# SparkFun_VR_IMU_Breakout_BNO086_QWIIC.net
KiCad netlist of a schematic drawn in EAGLE
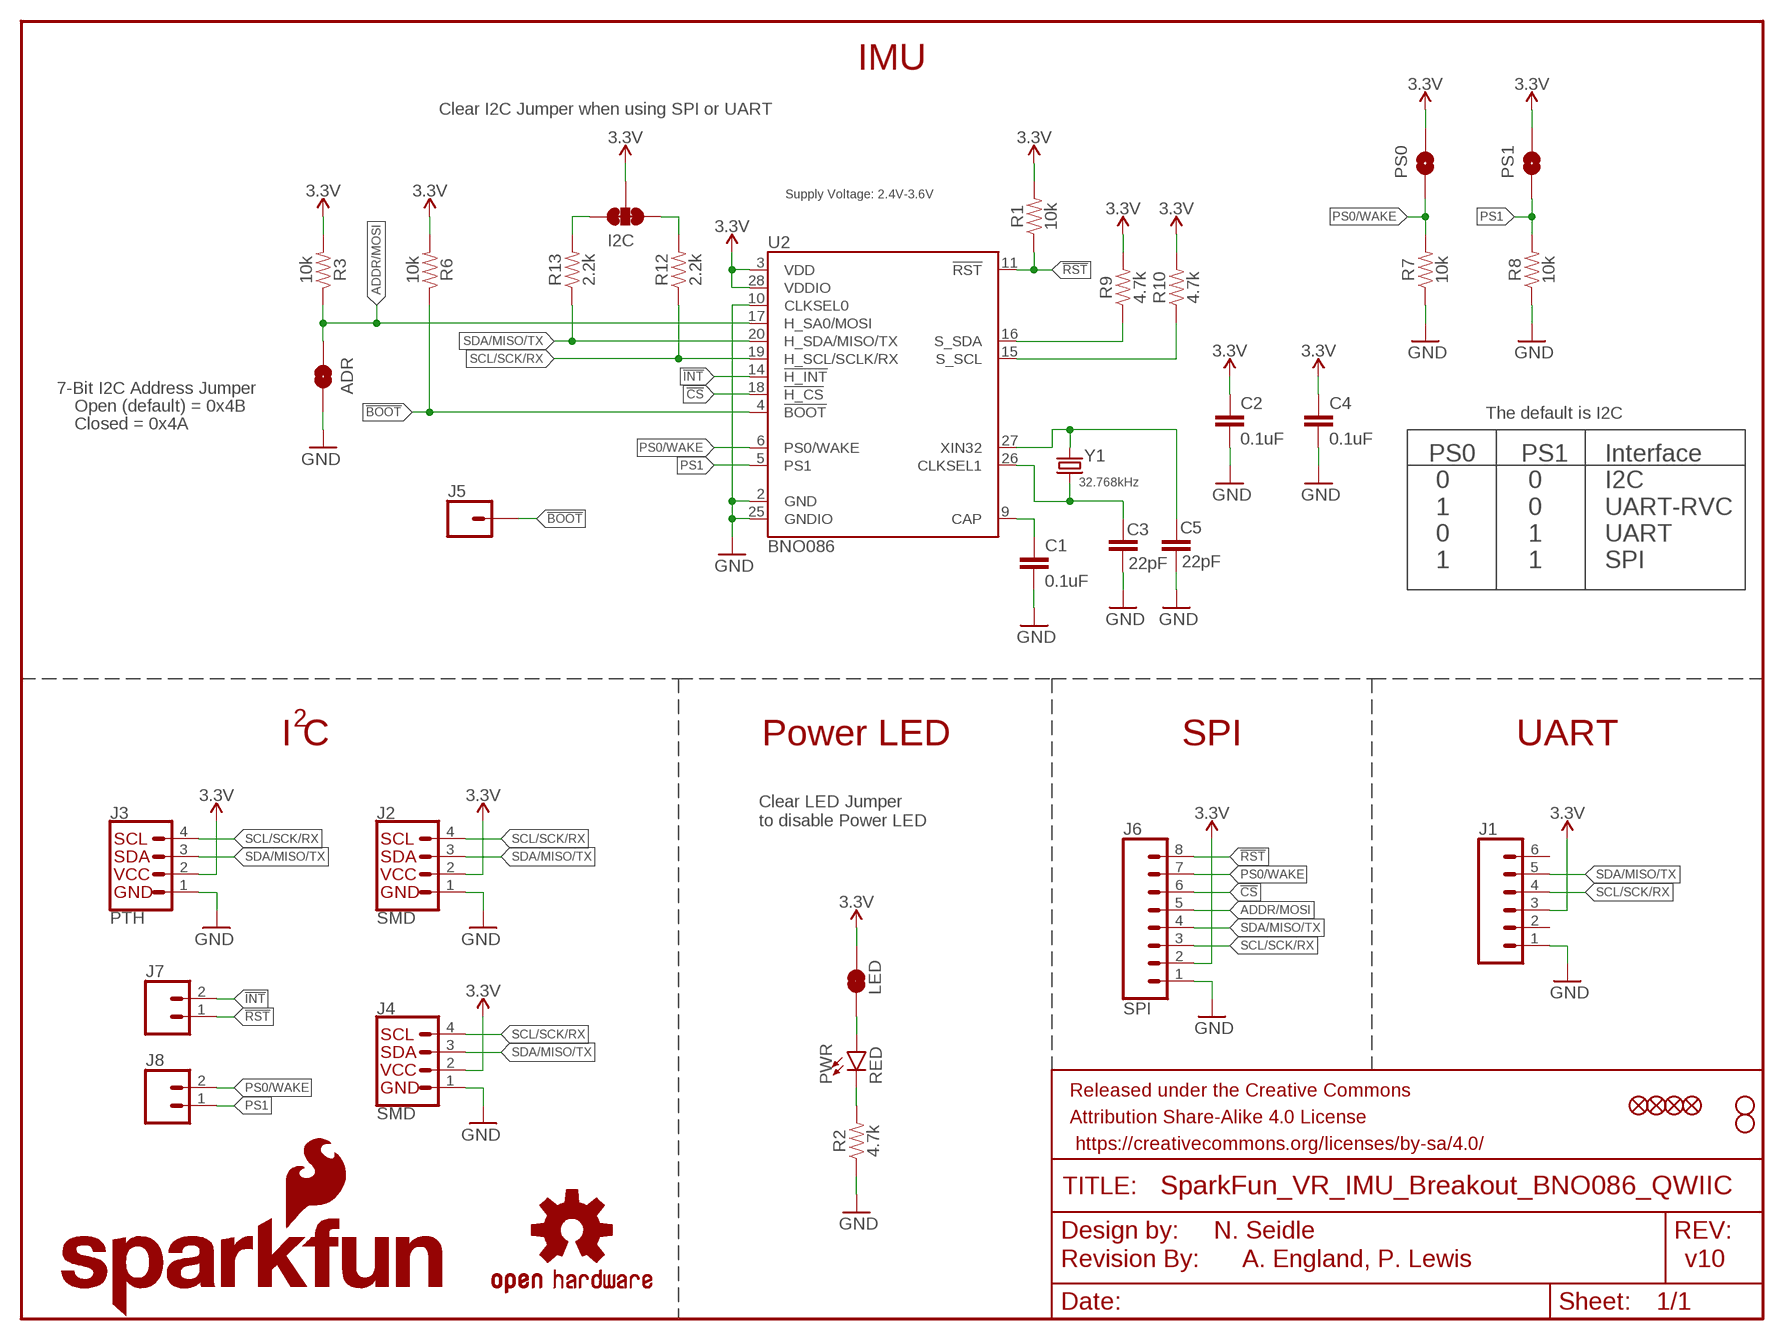
[diagram p0: schematic, sheet 1]

(export (version "E")
  (design (tool "Eeschema 10.0.6"))
  (components
    (comp (ref "ADR")
      (value "JUMPER-SMT_2_NO_SILK")
      (footprint "eagle-import:SMT-JUMPER_2_NO_SILK")
      (libsource (lib "eagle-import") (part "JUMPER-SMT_2_NO_SILK"))
    )
    (comp (ref "C1")
      (value "0.1uF")
      (footprint "eagle-import:0603")
      (libsource (lib "eagle-import") (part "0.1UF-0603-25V-(+80/-20%)"))
    )
    (comp (ref "C2")
      (value "0.1uF")
      (footprint "eagle-import:0603")
      (libsource (lib "eagle-import") (part "0.1UF-0603-25V-(+80/-20%)"))
    )
    (comp (ref "C3")
      (value "22pF")
      (footprint "eagle-import:0603")
      (libsource (lib "eagle-import") (part "22PF-0603-50V-5%"))
    )
    (comp (ref "C4")
      (value "0.1uF")
      (footprint "eagle-import:0603")
      (libsource (lib "eagle-import") (part "0.1UF-0603-25V-(+80/-20%)"))
    )
    (comp (ref "C5")
      (value "22pF")
      (footprint "eagle-import:0603")
      (libsource (lib "eagle-import") (part "22PF-0603-50V-5%"))
    )
    (comp (ref "FRAME1")
      (value "FRAME-LETTER")
      (footprint "eagle-import:CREATIVE_COMMONS")
      (libsource (lib "eagle-import") (part "FRAME-LETTER"))
    )
    (comp (ref "I2C")
      (value "JUMPER-SMT_3_2-NC_TRACE_SILK")
      (footprint "eagle-import:SMT-JUMPER_3_2-NC_TRACE_SILK")
      (libsource (lib "eagle-import") (part "JUMPER-SMT_3_2-NC_TRACE_SILK"))
    )
    (comp (ref "J1")
      (value "CONN_06NO_SILK_FEMALE_PTH")
      (footprint "eagle-import:1X06_NO_SILK")
      (libsource (lib "eagle-import") (part "CONN_06NO_SILK_FEMALE_PTH"))
    )
    (comp (ref "J2")
      (value "SMD")
      (footprint "eagle-import:JST04_1MM_RA")
      (libsource (lib "eagle-import") (part "QWIIC_CONNECTORJS-1MM"))
    )
    (comp (ref "J3")
      (value "PTH")
      (footprint "eagle-import:1X04_NO_SILK")
      (libsource (lib "eagle-import") (part "I2C_STANDARD_NO_SILK"))
    )
    (comp (ref "J4")
      (value "SMD")
      (footprint "eagle-import:JST04_1MM_RA")
      (libsource (lib "eagle-import") (part "QWIIC_CONNECTORJS-1MM"))
    )
    (comp (ref "J5")
      (value "CONN_01PTH_NO_SILK_YES_STOP")
      (footprint "eagle-import:1X01_NO_SILK")
      (libsource (lib "eagle-import") (part "CONN_01PTH_NO_SILK_YES_STOP"))
    )
    (comp (ref "J6")
      (value "SPI")
      (footprint "eagle-import:1X08_NO_SILK")
      (libsource (lib "eagle-import") (part "CONN_08NO_SILK_FEMALE_PTH"))
    )
    (comp (ref "J7")
      (value "CONN_021X02_NO_SILK")
      (footprint "eagle-import:1X02_NO_SILK")
      (libsource (lib "eagle-import") (part "CONN_021X02_NO_SILK"))
    )
    (comp (ref "J8")
      (value "CONN_021X02_NO_SILK")
      (footprint "eagle-import:1X02_NO_SILK")
      (libsource (lib "eagle-import") (part "CONN_021X02_NO_SILK"))
    )
    (comp (ref "JP1")
      (value "FIDUCIALUFIDUCIAL")
      (footprint "eagle-import:FIDUCIAL-MICRO")
      (libsource (lib "eagle-import") (part "FIDUCIALUFIDUCIAL"))
    )
    (comp (ref "JP2")
      (value "FIDUCIALUFIDUCIAL")
      (footprint "eagle-import:FIDUCIAL-MICRO")
      (libsource (lib "eagle-import") (part "FIDUCIALUFIDUCIAL"))
    )
    (comp (ref "JP3")
      (value "STAND-OFF")
      (footprint "eagle-import:STAND-OFF")
      (libsource (lib "eagle-import") (part "STAND-OFF"))
    )
    (comp (ref "JP4")
      (value "STAND-OFF")
      (footprint "eagle-import:STAND-OFF")
      (libsource (lib "eagle-import") (part "STAND-OFF"))
    )
    (comp (ref "JP5")
      (value "FIDUCIALUFIDUCIAL")
      (footprint "eagle-import:FIDUCIAL-MICRO")
      (libsource (lib "eagle-import") (part "FIDUCIALUFIDUCIAL"))
    )
    (comp (ref "JP6")
      (value "FIDUCIALUFIDUCIAL")
      (footprint "eagle-import:FIDUCIAL-MICRO")
      (libsource (lib "eagle-import") (part "FIDUCIALUFIDUCIAL"))
    )
    (comp (ref "LED")
      (value "JUMPER-SMT_2_NC_TRACE_SILK")
      (footprint "eagle-import:SMT-JUMPER_2_NC_TRACE_SILK")
      (libsource (lib "eagle-import") (part "JUMPER-SMT_2_NC_TRACE_SILK"))
    )
    (comp (ref "LOGO1")
      (value "OSHW-LOGOMINI")
      (footprint "eagle-import:OSHW-LOGO-MINI")
      (libsource (lib "eagle-import") (part "OSHW-LOGOMINI"))
    )
    (comp (ref "LOGO2")
      (value "REVISION")
      (footprint "eagle-import:REVISION")
      (libsource (lib "eagle-import") (part "REVISION"))
    )
    (comp (ref "LOGO4")
      (value "SFE_LOGO_FLAME.2_INCH")
      (footprint "eagle-import:SFE_LOGO_FLAME_.2")
      (libsource (lib "eagle-import") (part "SFE_LOGO_FLAME.2_INCH"))
    )
    (comp (ref "LOGO5")
      (value "SFE_LOGO_NAME_FLAME.1_INCH")
      (footprint "eagle-import:SFE_LOGO_NAME_FLAME_.1")
      (libsource (lib "eagle-import") (part "SFE_LOGO_NAME_FLAME.1_INCH"))
    )
    (comp (ref "PS0")
      (value "JUMPER-SMT_2_NO_SILK")
      (footprint "eagle-import:SMT-JUMPER_2_NO_SILK")
      (libsource (lib "eagle-import") (part "JUMPER-SMT_2_NO_SILK"))
    )
    (comp (ref "PS1")
      (value "JUMPER-SMT_2_NO_SILK")
      (footprint "eagle-import:SMT-JUMPER_2_NO_SILK")
      (libsource (lib "eagle-import") (part "JUMPER-SMT_2_NO_SILK"))
    )
    (comp (ref "PWR")
      (value "RED")
      (footprint "eagle-import:LED-0603")
      (libsource (lib "eagle-import") (part "LED-RED_0603-KB"))
    )
    (comp (ref "R1")
      (value "10k")
      (footprint "eagle-import:0603")
      (libsource (lib "eagle-import") (part "10KOHM-0603-1/10W-1%"))
    )
    (comp (ref "R2")
      (value "4.7k")
      (footprint "eagle-import:0603")
      (libsource (lib "eagle-import") (part "4.7KOHM-0603-1/10W-1%"))
    )
    (comp (ref "R3")
      (value "10k")
      (footprint "eagle-import:0603")
      (libsource (lib "eagle-import") (part "10KOHM-0603-1/10W-1%"))
    )
    (comp (ref "R6")
      (value "10k")
      (footprint "eagle-import:0603")
      (libsource (lib "eagle-import") (part "10KOHM-0603-1/10W-1%"))
    )
    (comp (ref "R7")
      (value "10k")
      (footprint "eagle-import:0603")
      (libsource (lib "eagle-import") (part "10KOHM-0603-1/10W-1%"))
    )
    (comp (ref "R8")
      (value "10k")
      (footprint "eagle-import:0603")
      (libsource (lib "eagle-import") (part "10KOHM-0603-1/10W-1%"))
    )
    (comp (ref "R9")
      (value "4.7k")
      (footprint "eagle-import:0603")
      (libsource (lib "eagle-import") (part "4.7KOHM-0603-1/10W-1%"))
    )
    (comp (ref "R10")
      (value "4.7k")
      (footprint "eagle-import:0603")
      (libsource (lib "eagle-import") (part "4.7KOHM-0603-1/10W-1%"))
    )
    (comp (ref "R12")
      (value "2.2k")
      (footprint "eagle-import:0603")
      (libsource (lib "eagle-import") (part "2.2KOHM-0603-1/10W-1%"))
    )
    (comp (ref "R13")
      (value "2.2k")
      (footprint "eagle-import:0603")
      (libsource (lib "eagle-import") (part "2.2KOHM-0603-1/10W-1%"))
    )
    (comp (ref "U2")
      (value "BNO086")
      (footprint "eagle-import:LGA-28")
      (libsource (lib "eagle-import") (part "BNO086"))
    )
    (comp (ref "Y1")
      (value "32.768kHz")
      (footprint "eagle-import:CRYSTAL-SMD-3.2X1.5MM")
      (libsource (lib "eagle-import") (part "CRYSTAL-32.768KHZSMD-3.2X1.5"))
    )
  )
  (nets
    (net (code "1") (name "/~{BOOT}") (class "Default")
      (node (ref "J5") (pin "1") (pinfunction "1_1") (pintype "passive"))
      (node (ref "R6") (pin "1") (pinfunction "1_1") (pintype "passive"))
      (node (ref "U2") (pin "4") (pinfunction "~{BOOT}_4") (pintype "bidirectional"))
    )
    (net (code "2") (name "/~{CS}") (class "Default")
      (node (ref "J6") (pin "6") (pinfunction "6_6") (pintype "passive"))
      (node (ref "U2") (pin "18") (pinfunction "~{H_CS}_18") (pintype "bidirectional"))
    )
    (net (code "3") (name "/~{INT}") (class "Default")
      (node (ref "J7") (pin "2") (pinfunction "2_2") (pintype "passive"))
      (node (ref "U2") (pin "14") (pinfunction "~{H_INT}_14") (pintype "bidirectional"))
    )
    (net (code "4") (name "/~{RST}") (class "Default")
      (node (ref "J6") (pin "8") (pinfunction "8_8") (pintype "passive"))
      (node (ref "J7") (pin "1") (pinfunction "1_1") (pintype "passive"))
      (node (ref "R1") (pin "1") (pinfunction "1_1") (pintype "passive"))
      (node (ref "U2") (pin "11") (pinfunction "~{RST}_11") (pintype "bidirectional"))
    )
    (net (code "5") (name "3.3V") (class "Default")
      (node (ref "C2") (pin "1") (pinfunction "1_1") (pintype "passive"))
      (node (ref "C4") (pin "1") (pinfunction "1_1") (pintype "passive"))
      (node (ref "I2C") (pin "2") (pinfunction "2_2") (pintype "passive"))
      (node (ref "J1") (pin "3") (pinfunction "3_3") (pintype "passive"))
      (node (ref "J2") (pin "2") (pinfunction "2_2") (pintype "power_in"))
      (node (ref "J3") (pin "2") (pinfunction "2_2") (pintype "power_in"))
      (node (ref "J4") (pin "2") (pinfunction "2_2") (pintype "power_in"))
      (node (ref "J6") (pin "2") (pinfunction "2_2") (pintype "passive"))
      (node (ref "LED") (pin "1") (pinfunction "1_1") (pintype "passive"))
      (node (ref "PS0") (pin "1") (pinfunction "1_1") (pintype "passive"))
      (node (ref "PS1") (pin "1") (pinfunction "1_1") (pintype "passive"))
      (node (ref "R1") (pin "2") (pinfunction "2_2") (pintype "passive"))
      (node (ref "R10") (pin "2") (pinfunction "2_2") (pintype "passive"))
      (node (ref "R3") (pin "2") (pinfunction "2_2") (pintype "passive"))
      (node (ref "R6") (pin "2") (pinfunction "2_2") (pintype "passive"))
      (node (ref "R9") (pin "2") (pinfunction "2_2") (pintype "passive"))
      (node (ref "U2") (pin "28") (pinfunction "VDDIO_28") (pintype "bidirectional"))
      (node (ref "U2") (pin "3") (pinfunction "VDD_3") (pintype "bidirectional"))
    )
    (net (code "6") (name "ADDR{slash}MOSI") (class "Default")
      (node (ref "ADR") (pin "2") (pinfunction "2_2") (pintype "passive"))
      (node (ref "J6") (pin "5") (pinfunction "5_5") (pintype "passive"))
      (node (ref "R3") (pin "1") (pinfunction "1_1") (pintype "passive"))
      (node (ref "U2") (pin "17") (pinfunction "H_SA0/MOSI_17") (pintype "bidirectional"))
    )
    (net (code "7") (name "GND") (class "Default")
      (node (ref "ADR") (pin "1") (pinfunction "1_1") (pintype "passive"))
      (node (ref "C1") (pin "2") (pinfunction "2_2") (pintype "passive"))
      (node (ref "C2") (pin "2") (pinfunction "2_2") (pintype "passive"))
      (node (ref "C3") (pin "2") (pinfunction "2_2") (pintype "passive"))
      (node (ref "C4") (pin "2") (pinfunction "2_2") (pintype "passive"))
      (node (ref "C5") (pin "2") (pinfunction "2_2") (pintype "passive"))
      (node (ref "J1") (pin "1") (pinfunction "1_1") (pintype "passive"))
      (node (ref "J2") (pin "1") (pinfunction "1_1") (pintype "power_in"))
      (node (ref "J3") (pin "1") (pinfunction "1_1") (pintype "power_in"))
      (node (ref "J4") (pin "1") (pinfunction "1_1") (pintype "power_in"))
      (node (ref "J6") (pin "1") (pinfunction "1_1") (pintype "passive"))
      (node (ref "R2") (pin "1") (pinfunction "1_1") (pintype "passive"))
      (node (ref "R7") (pin "1") (pinfunction "1_1") (pintype "passive"))
      (node (ref "R8") (pin "1") (pinfunction "1_1") (pintype "passive"))
      (node (ref "U2") (pin "10") (pinfunction "CLKSEL0_10") (pintype "bidirectional"))
      (node (ref "U2") (pin "2") (pinfunction "GND_2") (pintype "bidirectional"))
      (node (ref "U2") (pin "25") (pinfunction "GNDIO_25") (pintype "bidirectional"))
    )
    (net (code "8") (name "Net-(I2C-Pad1)") (class "Default")
      (node (ref "I2C") (pin "1") (pinfunction "1_1") (pintype "passive"))
      (node (ref "R12") (pin "2") (pinfunction "2_2") (pintype "passive"))
    )
    (net (code "9") (name "Net-(I2C-Pad3)") (class "Default")
      (node (ref "I2C") (pin "3") (pinfunction "3_3") (pintype "passive"))
      (node (ref "R13") (pin "2") (pinfunction "2_2") (pintype "passive"))
    )
    (net (code "10") (name "Net-(LED-Pad2)") (class "Default")
      (node (ref "LED") (pin "2") (pinfunction "2_2") (pintype "passive"))
      (node (ref "PWR") (pin "A") (pinfunction "A_A") (pintype "passive"))
    )
    (net (code "11") (name "Net-(PWR-PadC)") (class "Default")
      (node (ref "PWR") (pin "C") (pinfunction "C_C") (pintype "passive"))
      (node (ref "R2") (pin "2") (pinfunction "2_2") (pintype "passive"))
    )
    (net (code "12") (name "Net-(U2-CAP)") (class "Default")
      (node (ref "C1") (pin "1") (pinfunction "1_1") (pintype "passive"))
      (node (ref "U2") (pin "9") (pinfunction "CAP_9") (pintype "bidirectional"))
    )
    (net (code "13") (name "Net-(U2-CLKSEL1)") (class "Default")
      (node (ref "C3") (pin "1") (pinfunction "1_1") (pintype "passive"))
      (node (ref "U2") (pin "26") (pinfunction "CLKSEL1_26") (pintype "bidirectional"))
      (node (ref "Y1") (pin "P$1") (pinfunction "1_P$1") (pintype "passive"))
    )
    (net (code "14") (name "Net-(U2-S_SCL)") (class "Default")
      (node (ref "R10") (pin "1") (pinfunction "1_1") (pintype "passive"))
      (node (ref "U2") (pin "15") (pinfunction "S_SCL_15") (pintype "bidirectional"))
    )
    (net (code "15") (name "Net-(U2-S_SDA)") (class "Default")
      (node (ref "R9") (pin "1") (pinfunction "1_1") (pintype "passive"))
      (node (ref "U2") (pin "16") (pinfunction "S_SDA_16") (pintype "bidirectional"))
    )
    (net (code "16") (name "Net-(U2-XIN32)") (class "Default")
      (node (ref "C5") (pin "1") (pinfunction "1_1") (pintype "passive"))
      (node (ref "U2") (pin "27") (pinfunction "XIN32_27") (pintype "bidirectional"))
      (node (ref "Y1") (pin "P$2") (pinfunction "2_P$2") (pintype "passive"))
    )
    (net (code "17") (name "PS0{slash}WAKE") (class "Default")
      (node (ref "J6") (pin "7") (pinfunction "7_7") (pintype "passive"))
      (node (ref "J8") (pin "2") (pinfunction "2_2") (pintype "passive"))
      (node (ref "PS0") (pin "2") (pinfunction "2_2") (pintype "passive"))
      (node (ref "R7") (pin "2") (pinfunction "2_2") (pintype "passive"))
      (node (ref "U2") (pin "6") (pinfunction "PS0/WAKE_6") (pintype "bidirectional"))
    )
    (net (code "18") (name "PS1") (class "Default")
      (node (ref "J8") (pin "1") (pinfunction "1_1") (pintype "passive"))
      (node (ref "PS1") (pin "2") (pinfunction "2_2") (pintype "passive"))
      (node (ref "R8") (pin "2") (pinfunction "2_2") (pintype "passive"))
      (node (ref "U2") (pin "5") (pinfunction "PS1_5") (pintype "bidirectional"))
    )
    (net (code "19") (name "SCL{slash}SCK{slash}RX") (class "Default")
      (node (ref "J1") (pin "4") (pinfunction "4_4") (pintype "passive"))
      (node (ref "J2") (pin "4") (pinfunction "4_4") (pintype "passive"))
      (node (ref "J3") (pin "4") (pinfunction "4_4") (pintype "passive"))
      (node (ref "J4") (pin "4") (pinfunction "4_4") (pintype "passive"))
      (node (ref "J6") (pin "3") (pinfunction "3_3") (pintype "passive"))
      (node (ref "R12") (pin "1") (pinfunction "1_1") (pintype "passive"))
      (node (ref "U2") (pin "19") (pinfunction "H_SCL/SCLK/RX_19") (pintype "bidirectional"))
    )
    (net (code "20") (name "SDA{slash}MISO{slash}TX") (class "Default")
      (node (ref "J1") (pin "5") (pinfunction "5_5") (pintype "passive"))
      (node (ref "J2") (pin "3") (pinfunction "3_3") (pintype "passive"))
      (node (ref "J3") (pin "3") (pinfunction "3_3") (pintype "passive"))
      (node (ref "J4") (pin "3") (pinfunction "3_3") (pintype "passive"))
      (node (ref "J6") (pin "4") (pinfunction "4_4") (pintype "passive"))
      (node (ref "R13") (pin "1") (pinfunction "1_1") (pintype "passive"))
      (node (ref "U2") (pin "20") (pinfunction "H_SDA/MISO/TX_20") (pintype "bidirectional"))
    )
    (net (code "21") (name "unconnected-(J1-Pad2)") (class "Default")
      (node (ref "J1") (pin "2") (pinfunction "2_2") (pintype "passive"))
    )
    (net (code "22") (name "unconnected-(J1-Pad6)") (class "Default")
      (node (ref "J1") (pin "6") (pinfunction "6_6") (pintype "passive"))
    )
  )
)
